# v0_3.net
KiCad netlist of a schematic drawn in EAGLE
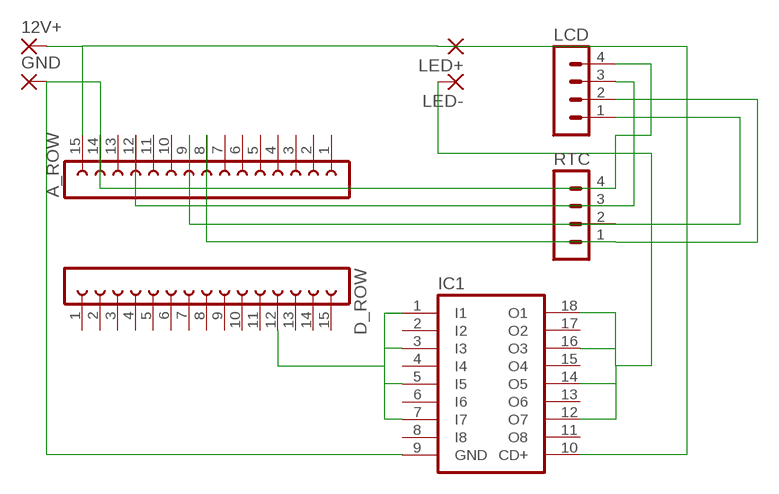
[diagram p0: schematic, sheet 1]

(export (version "E")
  (design (tool "Eeschema 10.0.6"))
  (components
    (comp (ref "12V+")
      (value "3,17/1,3")
      (footprint "eagle-import:3,17_1,3")
      (libsource (lib "eagle-import") (part "3,17/1,3"))
    )
    (comp (ref "A_ROW")
      (value "FE15-1")
      (footprint "eagle-import:FE15")
      (libsource (lib "eagle-import") (part "FE15-1"))
    )
    (comp (ref "D_ROW")
      (value "FE15-1")
      (footprint "eagle-import:FE15")
      (libsource (lib "eagle-import") (part "FE15-1"))
    )
    (comp (ref "GND")
      (value "3,17/1,3")
      (footprint "eagle-import:3,17_1,3")
      (libsource (lib "eagle-import") (part "3,17/1,3"))
    )
    (comp (ref "IC1")
      (value "ULN2803A")
      (footprint "eagle-import:DIL18")
      (libsource (lib "eagle-import") (part "ULN2803A"))
    )
    (comp (ref "LCD")
      (value "MA04-1")
      (footprint "eagle-import:MA04-1")
      (libsource (lib "eagle-import") (part "MA04-1"))
    )
    (comp (ref "LED+")
      (value "3,17/1,3")
      (footprint "eagle-import:3,17_1,3")
      (libsource (lib "eagle-import") (part "3,17/1,3"))
    )
    (comp (ref "LED-")
      (value "3,17/1,3")
      (footprint "eagle-import:3,17_1,3")
      (libsource (lib "eagle-import") (part "3,17/1,3"))
    )
    (comp (ref "RTC")
      (value "MA04-1")
      (footprint "eagle-import:MA04-1")
      (libsource (lib "eagle-import") (part "MA04-1"))
    )
  )
  (nets
    (net (code "1") (name "Net-(12V+-P)") (class "Default")
      (node (ref "12V+") (pin "1") (pinfunction "P_1") (pintype "passive"))
      (node (ref "A_ROW") (pin "15") (pinfunction "15_15") (pintype "passive"))
      (node (ref "IC1") (pin "10") (pinfunction "CD+_10") (pintype "passive"))
      (node (ref "LED+") (pin "1") (pinfunction "P_1") (pintype "passive"))
    )
    (net (code "2") (name "Net-(A_ROW-Pad8)") (class "Default")
      (node (ref "A_ROW") (pin "8") (pinfunction "8_8") (pintype "passive"))
      (node (ref "LCD") (pin "2") (pinfunction "2_2") (pintype "passive"))
      (node (ref "RTC") (pin "1") (pinfunction "1_1") (pintype "passive"))
    )
    (net (code "3") (name "Net-(A_ROW-Pad9)") (class "Default")
      (node (ref "A_ROW") (pin "9") (pinfunction "9_9") (pintype "passive"))
      (node (ref "LCD") (pin "1") (pinfunction "1_1") (pintype "passive"))
      (node (ref "RTC") (pin "2") (pinfunction "2_2") (pintype "passive"))
    )
    (net (code "4") (name "Net-(A_ROW-Pad12)") (class "Default")
      (node (ref "A_ROW") (pin "12") (pinfunction "12_12") (pintype "passive"))
      (node (ref "LCD") (pin "3") (pinfunction "3_3") (pintype "passive"))
      (node (ref "RTC") (pin "3") (pinfunction "3_3") (pintype "passive"))
    )
    (net (code "5") (name "Net-(GND-P)") (class "Default")
      (node (ref "A_ROW") (pin "14") (pinfunction "14_14") (pintype "passive"))
      (node (ref "GND") (pin "1") (pinfunction "P_1") (pintype "passive"))
      (node (ref "IC1") (pin "9") (pinfunction "GND_9") (pintype "power_in"))
      (node (ref "LCD") (pin "4") (pinfunction "4_4") (pintype "passive"))
      (node (ref "RTC") (pin "4") (pinfunction "4_4") (pintype "passive"))
    )
    (net (code "6") (name "Net-(IC1-I1)") (class "Default")
      (node (ref "D_ROW") (pin "12") (pinfunction "12_12") (pintype "passive"))
      (node (ref "IC1") (pin "1") (pinfunction "I1_1") (pintype "input"))
      (node (ref "IC1") (pin "3") (pinfunction "I3_3") (pintype "input"))
      (node (ref "IC1") (pin "5") (pinfunction "I5_5") (pintype "input"))
      (node (ref "IC1") (pin "7") (pinfunction "I7_7") (pintype "input"))
    )
    (net (code "7") (name "Net-(IC1-O1)") (class "Default")
      (node (ref "IC1") (pin "12") (pinfunction "O7_12") (pintype "open_collector"))
      (node (ref "IC1") (pin "14") (pinfunction "O5_14") (pintype "open_collector"))
      (node (ref "IC1") (pin "16") (pinfunction "O3_16") (pintype "open_collector"))
      (node (ref "IC1") (pin "18") (pinfunction "O1_18") (pintype "open_collector"))
      (node (ref "LED-") (pin "1") (pinfunction "P_1") (pintype "passive"))
    )
    (net (code "8") (name "unconnected-(A_ROW-Pad1)") (class "Default")
      (node (ref "A_ROW") (pin "1") (pinfunction "1_1") (pintype "passive"))
    )
    (net (code "9") (name "unconnected-(A_ROW-Pad2)") (class "Default")
      (node (ref "A_ROW") (pin "2") (pinfunction "2_2") (pintype "passive"))
    )
    (net (code "10") (name "unconnected-(A_ROW-Pad3)") (class "Default")
      (node (ref "A_ROW") (pin "3") (pinfunction "3_3") (pintype "passive"))
    )
    (net (code "11") (name "unconnected-(A_ROW-Pad4)") (class "Default")
      (node (ref "A_ROW") (pin "4") (pinfunction "4_4") (pintype "passive"))
    )
    (net (code "12") (name "unconnected-(A_ROW-Pad5)") (class "Default")
      (node (ref "A_ROW") (pin "5") (pinfunction "5_5") (pintype "passive"))
    )
    (net (code "13") (name "unconnected-(A_ROW-Pad6)") (class "Default")
      (node (ref "A_ROW") (pin "6") (pinfunction "6_6") (pintype "passive"))
    )
    (net (code "14") (name "unconnected-(A_ROW-Pad7)") (class "Default")
      (node (ref "A_ROW") (pin "7") (pinfunction "7_7") (pintype "passive"))
    )
    (net (code "15") (name "unconnected-(A_ROW-Pad10)") (class "Default")
      (node (ref "A_ROW") (pin "10") (pinfunction "10_10") (pintype "passive"))
    )
    (net (code "16") (name "unconnected-(A_ROW-Pad11)") (class "Default")
      (node (ref "A_ROW") (pin "11") (pinfunction "11_11") (pintype "passive"))
    )
    (net (code "17") (name "unconnected-(A_ROW-Pad13)") (class "Default")
      (node (ref "A_ROW") (pin "13") (pinfunction "13_13") (pintype "passive"))
    )
    (net (code "18") (name "unconnected-(D_ROW-Pad1)") (class "Default")
      (node (ref "D_ROW") (pin "1") (pinfunction "1_1") (pintype "passive"))
    )
    (net (code "19") (name "unconnected-(D_ROW-Pad2)") (class "Default")
      (node (ref "D_ROW") (pin "2") (pinfunction "2_2") (pintype "passive"))
    )
    (net (code "20") (name "unconnected-(D_ROW-Pad3)") (class "Default")
      (node (ref "D_ROW") (pin "3") (pinfunction "3_3") (pintype "passive"))
    )
    (net (code "21") (name "unconnected-(D_ROW-Pad4)") (class "Default")
      (node (ref "D_ROW") (pin "4") (pinfunction "4_4") (pintype "passive"))
    )
    (net (code "22") (name "unconnected-(D_ROW-Pad5)") (class "Default")
      (node (ref "D_ROW") (pin "5") (pinfunction "5_5") (pintype "passive"))
    )
    (net (code "23") (name "unconnected-(D_ROW-Pad6)") (class "Default")
      (node (ref "D_ROW") (pin "6") (pinfunction "6_6") (pintype "passive"))
    )
    (net (code "24") (name "unconnected-(D_ROW-Pad7)") (class "Default")
      (node (ref "D_ROW") (pin "7") (pinfunction "7_7") (pintype "passive"))
    )
    (net (code "25") (name "unconnected-(D_ROW-Pad8)") (class "Default")
      (node (ref "D_ROW") (pin "8") (pinfunction "8_8") (pintype "passive"))
    )
    (net (code "26") (name "unconnected-(D_ROW-Pad9)") (class "Default")
      (node (ref "D_ROW") (pin "9") (pinfunction "9_9") (pintype "passive"))
    )
    (net (code "27") (name "unconnected-(D_ROW-Pad10)") (class "Default")
      (node (ref "D_ROW") (pin "10") (pinfunction "10_10") (pintype "passive"))
    )
    (net (code "28") (name "unconnected-(D_ROW-Pad11)") (class "Default")
      (node (ref "D_ROW") (pin "11") (pinfunction "11_11") (pintype "passive"))
    )
    (net (code "29") (name "unconnected-(D_ROW-Pad13)") (class "Default")
      (node (ref "D_ROW") (pin "13") (pinfunction "13_13") (pintype "passive"))
    )
    (net (code "30") (name "unconnected-(D_ROW-Pad14)") (class "Default")
      (node (ref "D_ROW") (pin "14") (pinfunction "14_14") (pintype "passive"))
    )
    (net (code "31") (name "unconnected-(D_ROW-Pad15)") (class "Default")
      (node (ref "D_ROW") (pin "15") (pinfunction "15_15") (pintype "passive"))
    )
    (net (code "32") (name "unconnected-(IC1-I2-Pad2)") (class "Default")
      (node (ref "IC1") (pin "2") (pinfunction "I2_2") (pintype "input"))
    )
    (net (code "33") (name "unconnected-(IC1-I4-Pad4)") (class "Default")
      (node (ref "IC1") (pin "4") (pinfunction "I4_4") (pintype "input"))
    )
    (net (code "34") (name "unconnected-(IC1-I6-Pad6)") (class "Default")
      (node (ref "IC1") (pin "6") (pinfunction "I6_6") (pintype "input"))
    )
    (net (code "35") (name "unconnected-(IC1-I8-Pad8)") (class "Default")
      (node (ref "IC1") (pin "8") (pinfunction "I8_8") (pintype "input"))
    )
    (net (code "36") (name "unconnected-(IC1-O2-Pad17)") (class "Default")
      (node (ref "IC1") (pin "17") (pinfunction "O2_17") (pintype "open_collector"))
    )
    (net (code "37") (name "unconnected-(IC1-O4-Pad15)") (class "Default")
      (node (ref "IC1") (pin "15") (pinfunction "O4_15") (pintype "open_collector"))
    )
    (net (code "38") (name "unconnected-(IC1-O6-Pad13)") (class "Default")
      (node (ref "IC1") (pin "13") (pinfunction "O6_13") (pintype "open_collector"))
    )
    (net (code "39") (name "unconnected-(IC1-O8-Pad11)") (class "Default")
      (node (ref "IC1") (pin "11") (pinfunction "O8_11") (pintype "open_collector"))
    )
  )
)
